# Stepper_Motor_IC_Circuit.net
KiCad netlist of a schematic drawn in Altium Designer
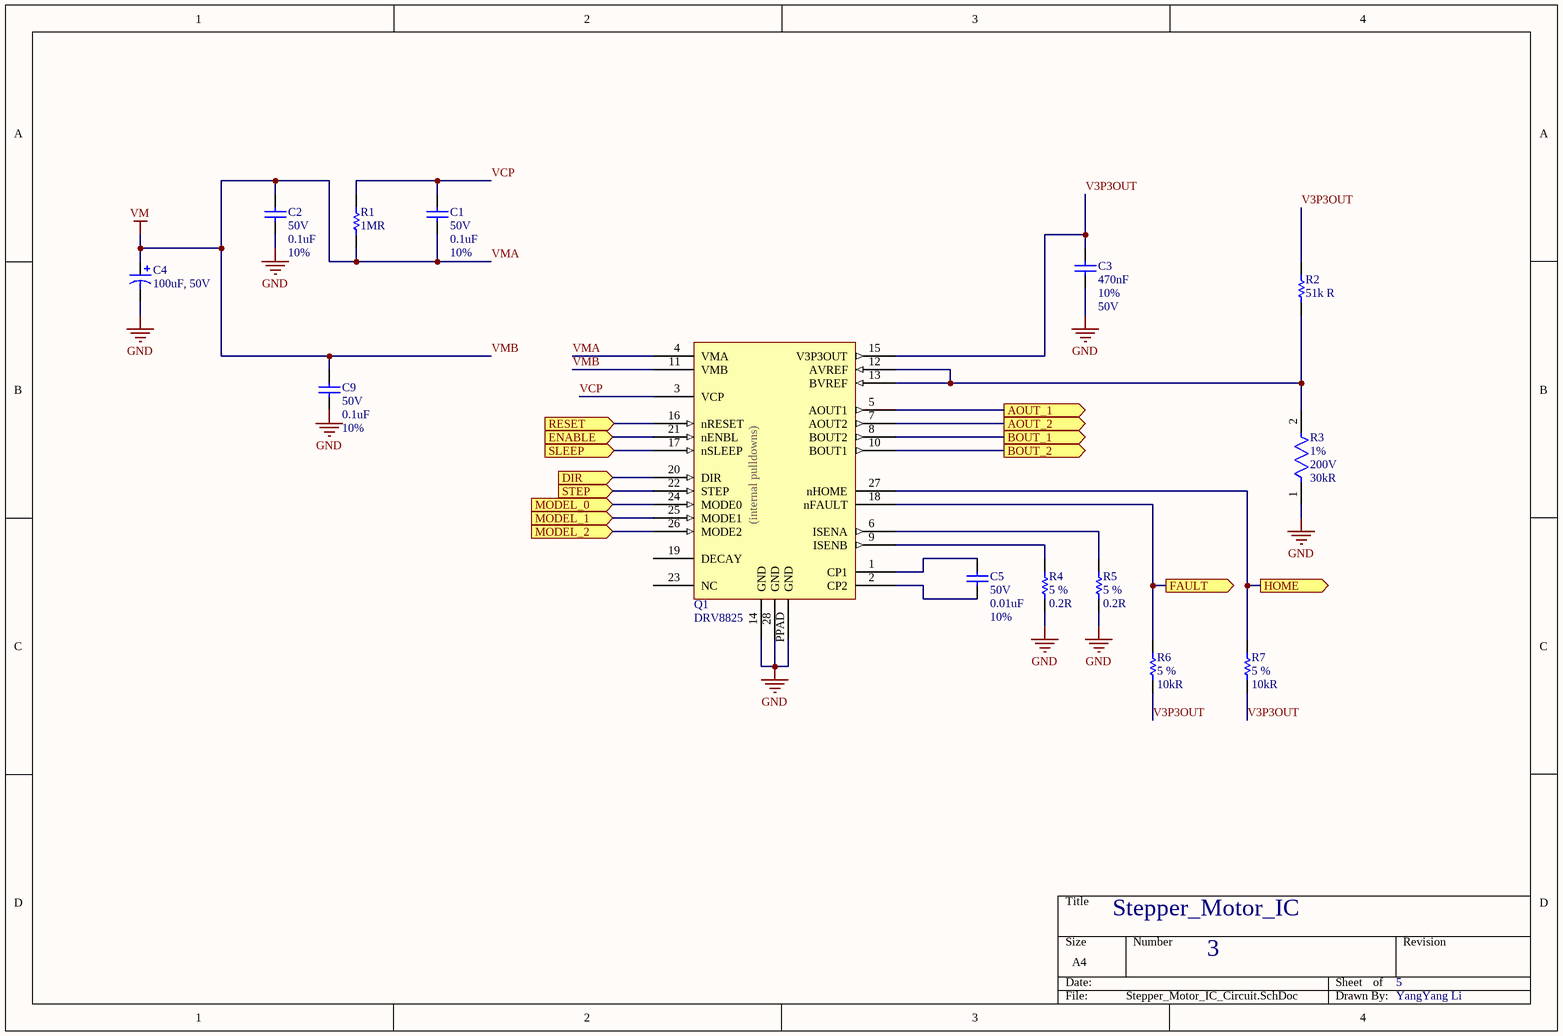
[diagram p0: Stepper_Motor_IC_Circuit.SchDoc]

(export (version "E")
  (design (tool "Eeschema 10.0.6"))
  (components
    (comp (ref "C1")
      (value "C1206C103K5RACTU")
      (footprint "KEMT-1206-2_L")
      (fields
        (field (name "VOLTAGE RATING") "50V")
        (field (name "MANUFACTURER") "Kemet")
        (field (name "CAPACITANCE") "0.1uF")
        (field (name "TOLERANCE") "10%")
      )
      (libsource (lib "Altium Content Vault") (part "CAP-NP-2"))
    )
    (comp (ref "C2")
      (value "C1206C103K5RACTU")
      (footprint "KEMT-1206-2_L")
      (fields
        (field (name "VOLTAGE RATING") "50V")
        (field (name "MANUFACTURER") "Kemet")
        (field (name "CAPACITANCE") "0.1uF")
        (field (name "TOLERANCE") "10%")
      )
      (libsource (lib "Altium Content Vault") (part "CAP-NP-2"))
    )
    (comp (ref "C3")
      (value "1206C474K5RACTU")
      (footprint "CAPC3216X100X50NL20T25")
      (description "Chip Capacitor, 470 nF, +/- 10%, 50 V, -55 to 125 degC, 1206 (3216 Metric), RoHS, Tape and Reel")
      (fields
        (field (name "MANUFACTURER") "Kemet")
        (field (name "CAPACITANCE - NF") "470nF")
        (field (name "TOLERANCE") "10%")
        (field (name "VOLTAGE RATING") "50V")
      )
      (libsource (lib "Altium Content Vault") (part "CAP-NP-2"))
    )
    (comp (ref "C4")
      (value "100uF, 50V")
      (footprint "Capacitor radial 8mm")
      (description "Electrolytic Capacitor, 100 µF, 50 V, ± 20%, Radial Leaded, 8 mm")
      (libsource (lib "*") (part "Cap 100uF, 50V, THT radial"))
    )
    (comp (ref "C5")
      (value "C1206C103K5RACTU")
      (footprint "KEMT-1206-2_L")
      (fields
        (field (name "VOLTAGE RATING") "50V")
        (field (name "MANUFACTURER") "Kemet")
        (field (name "CAPACITANCE") "0.01uF")
        (field (name "TOLERANCE") "10%")
      )
      (libsource (lib "Altium Content Vault") (part "CAP-NP-2"))
    )
    (comp (ref "C9")
      (value "C1206C103K5RACTU")
      (footprint "KEMT-1206-2_L")
      (fields
        (field (name "VOLTAGE RATING") "50V")
        (field (name "MANUFACTURER") "Kemet")
        (field (name "CAPACITANCE") "0.1uF")
        (field (name "TOLERANCE") "10%")
      )
      (libsource (lib "Altium Content Vault") (part "CAP-NP-2"))
    )
    (comp (ref "Q1")
      (value "DRV8825")
      (footprint "DRV8825 HTSSOP")
      (description "TI DRV8825 Stepper Motor Controller IC")
      (libsource (lib "*") (part "Stepper motor driver DRV8825"))
    )
    (comp (ref "R1")
      (value "ERJ-8ENF1004V")
      (footprint "RESC3216X70X50NL05T20")
      (fields (field (name "MANUFACTURER") "Panasonic") (field (name "RESISTANCE") "1MR"))
      (libsource (lib "Altium Content Vault") (part "RES"))
    )
    (comp (ref "R2")
      (value "51k R")
      (footprint "RESC3216X60X45NL10T20")
      (description "CRCW120651K0JNEA")
      (fields (field (name "MANUFACTURER") "Vishay Dale"))
      (libsource (lib "Altium Content Vault") (part "RES"))
    )
    (comp (ref "R3")
      (value "CR1206-FX-3002ELF")
      (footprint "FP-CR1206-MFG")
      (description "Thick Film Chip Resistors 1206 30kΩ 0.25W 1% 100ppm/°C")
      (fields
        (field (name "TOLERANCE") "1%")
        (field (name "VOLTAGE RATING") "200V")
        (field (name "RESISTANCE") "30kR")
      )
      (libsource (lib "Altium Content Vault") (part "1029c3af85768c4190bb7ad29bc67b5"))
    )
    (comp (ref "R4")
      (value "0.2R")
      (footprint "RESC1206(3216)_L")
      (description "0.2R 0.25W 5% 1206 (3216 Metric)  SMD")
      (fields
        (field (name "TOLERANCE") "5 %")
        (field (name "POWER") "0.25 W")
        (field (name "Comment") "0.2R 5% 1206(3216)")
      )
      (libsource (lib "Altium Content Vault") (part "RES"))
    )
    (comp (ref "R5")
      (value "0.2R")
      (footprint "RESC1206(3216)_L")
      (description "0.2R 0.25W 5% 1206 (3216 Metric)  SMD")
      (fields
        (field (name "TOLERANCE") "5 %")
        (field (name "POWER") "0.25 W")
        (field (name "Comment") "0.2R 5% 1206(3216)")
      )
      (libsource (lib "Altium Content Vault") (part "RES"))
    )
    (comp (ref "R6")
      (value "10kR")
      (footprint "RESC1206(3216)_M")
      (description "10K 0.25W 5% 1206 (3216 Metric)  SMD")
      (fields
        (field (name "POWER") "0.25 W")
        (field (name "TOLERANCE") "5 %")
        (field (name "Comment") "10K 5% 1206(3216)")
      )
      (libsource (lib "Altium Content Vault") (part "RES"))
    )
    (comp (ref "R7")
      (value "10kR")
      (footprint "RESC1206(3216)_M")
      (description "10K 0.25W 5% 1206 (3216 Metric)  SMD")
      (fields
        (field (name "POWER") "0.25 W")
        (field (name "TOLERANCE") "5 %")
        (field (name "Comment") "10K 5% 1206(3216)")
      )
      (libsource (lib "Altium Content Vault") (part "RES"))
    )
  )
  (nets
    (net (code "1") (name "/AOUT_1") (class "Default")
      (node (ref "Q1") (pin "5") (pinfunction "AOUT1_5") (pintype "output"))
    )
    (net (code "2") (name "/AOUT_2") (class "Default")
      (node (ref "Q1") (pin "7") (pinfunction "AOUT2_7") (pintype "output"))
    )
    (net (code "3") (name "/BOUT_1") (class "Default")
      (node (ref "Q1") (pin "8") (pinfunction "BOUT2_8") (pintype "output"))
    )
    (net (code "4") (name "/BOUT_2") (class "Default")
      (node (ref "Q1") (pin "10") (pinfunction "BOUT1_10") (pintype "output"))
    )
    (net (code "5") (name "/DIR") (class "Default")
      (node (ref "Q1") (pin "20") (pinfunction "DIR_20") (pintype "input"))
    )
    (net (code "6") (name "/ENABLE") (class "Default")
      (node (ref "Q1") (pin "21") (pinfunction "nENBL_21") (pintype "input"))
    )
    (net (code "7") (name "/FAULT") (class "Default")
      (node (ref "Q1") (pin "18") (pinfunction "nFAULT_18") (pintype "open_collector"))
      (node (ref "R6") (pin "2") (pinfunction "2_2") (pintype "passive"))
    )
    (net (code "8") (name "/HOME") (class "Default")
      (node (ref "Q1") (pin "27") (pinfunction "nHOME_27") (pintype "open_collector"))
      (node (ref "R7") (pin "2") (pinfunction "2_2") (pintype "passive"))
    )
    (net (code "9") (name "/MODEL_0") (class "Default")
      (node (ref "Q1") (pin "24") (pinfunction "MODE0_24") (pintype "input"))
    )
    (net (code "10") (name "/MODEL_1") (class "Default")
      (node (ref "Q1") (pin "25") (pinfunction "MODE1_25") (pintype "input"))
    )
    (net (code "11") (name "/MODEL_2") (class "Default")
      (node (ref "Q1") (pin "26") (pinfunction "MODE2_26") (pintype "input"))
    )
    (net (code "12") (name "/RESET") (class "Default")
      (node (ref "Q1") (pin "16") (pinfunction "nRESET_16") (pintype "input"))
    )
    (net (code "13") (name "/SLEEP") (class "Default")
      (node (ref "Q1") (pin "17") (pinfunction "nSLEEP_17") (pintype "input"))
    )
    (net (code "14") (name "/STEP") (class "Default")
      (node (ref "Q1") (pin "22") (pinfunction "STEP_22") (pintype "input"))
    )
    (net (code "15") (name "/V3P3OUT") (class "Default")
      (node (ref "C3") (pin "1") (pinfunction "1_1") (pintype "passive"))
      (node (ref "Q1") (pin "15") (pinfunction "V3P3OUT_15") (pintype "output"))
      (node (ref "R2") (pin "2") (pinfunction "2_2") (pintype "passive"))
      (node (ref "R6") (pin "1") (pinfunction "1_1") (pintype "passive"))
      (node (ref "R7") (pin "1") (pinfunction "1_1") (pintype "passive"))
    )
    (net (code "16") (name "/VCP") (class "Default")
      (node (ref "C1") (pin "1") (pinfunction "1_1") (pintype "passive"))
      (node (ref "Q1") (pin "3") (pinfunction "VCP_3") (pintype "power_in"))
      (node (ref "R1") (pin "1") (pinfunction "1_1") (pintype "passive"))
    )
    (net (code "17") (name "GND") (class "Default")
      (node (ref "C2") (pin "2") (pinfunction "2_2") (pintype "passive"))
      (node (ref "C3") (pin "2") (pinfunction "2_2") (pintype "passive"))
      (node (ref "C4") (pin "2") (pinfunction "2_2") (pintype "passive"))
      (node (ref "C9") (pin "2") (pinfunction "2_2") (pintype "passive"))
      (node (ref "Q1") (pin "14") (pinfunction "GND_14") (pintype "power_in"))
      (node (ref "Q1") (pin "28") (pinfunction "GND_28") (pintype "power_in"))
      (node (ref "Q1") (pin "PPAD") (pinfunction "GND_PPAD") (pintype "power_in"))
      (node (ref "R3") (pin "1") (pinfunction "1_1") (pintype "passive"))
      (node (ref "R4") (pin "2") (pinfunction "2_2") (pintype "passive"))
      (node (ref "R5") (pin "2") (pinfunction "2_2") (pintype "passive"))
    )
    (net (code "18") (name "Net-(Q1-AVREF)") (class "Default")
      (node (ref "Q1") (pin "12") (pinfunction "AVREF_12") (pintype "input"))
      (node (ref "Q1") (pin "13") (pinfunction "BVREF_13") (pintype "input"))
      (node (ref "R2") (pin "1") (pinfunction "1_1") (pintype "passive"))
      (node (ref "R3") (pin "2") (pinfunction "2_2") (pintype "passive"))
    )
    (net (code "19") (name "Net-(Q1-CP1)") (class "Default")
      (node (ref "C5") (pin "2") (pinfunction "2_2") (pintype "passive"))
      (node (ref "Q1") (pin "1") (pinfunction "CP1_1") (pintype "power_in"))
    )
    (net (code "20") (name "Net-(Q1-CP2)") (class "Default")
      (node (ref "C5") (pin "1") (pinfunction "1_1") (pintype "passive"))
      (node (ref "Q1") (pin "2") (pinfunction "CP2_2") (pintype "power_in"))
    )
    (net (code "21") (name "Net-(Q1-ISENA)") (class "Default")
      (node (ref "Q1") (pin "6") (pinfunction "ISENA_6") (pintype "output"))
      (node (ref "R5") (pin "1") (pinfunction "1_1") (pintype "passive"))
    )
    (net (code "22") (name "Net-(Q1-ISENB)") (class "Default")
      (node (ref "Q1") (pin "9") (pinfunction "ISENB_9") (pintype "output"))
      (node (ref "R4") (pin "1") (pinfunction "1_1") (pintype "passive"))
    )
    (net (code "23") (name "VM") (class "Default")
      (node (ref "C1") (pin "2") (pinfunction "2_2") (pintype "passive"))
      (node (ref "C2") (pin "1") (pinfunction "1_1") (pintype "passive"))
      (node (ref "C4") (pin "1") (pinfunction "1_1") (pintype "passive"))
      (node (ref "C9") (pin "1") (pinfunction "1_1") (pintype "passive"))
      (node (ref "Q1") (pin "11") (pinfunction "VMB_11") (pintype "power_in"))
      (node (ref "Q1") (pin "4") (pinfunction "VMA_4") (pintype "power_in"))
      (node (ref "R1") (pin "2") (pinfunction "2_2") (pintype "passive"))
    )
    (net (code "24") (name "unconnected-(Q1-DECAY-Pad19)") (class "Default")
      (node (ref "Q1") (pin "19") (pinfunction "DECAY_19") (pintype "passive"))
    )
    (net (code "25") (name "unconnected-(Q1-NC-Pad23)") (class "Default")
      (node (ref "Q1") (pin "23") (pinfunction "NC_23") (pintype "passive"))
    )
  )
)
